# brain.net
KiCad netlist of a schematic drawn in EAGLE
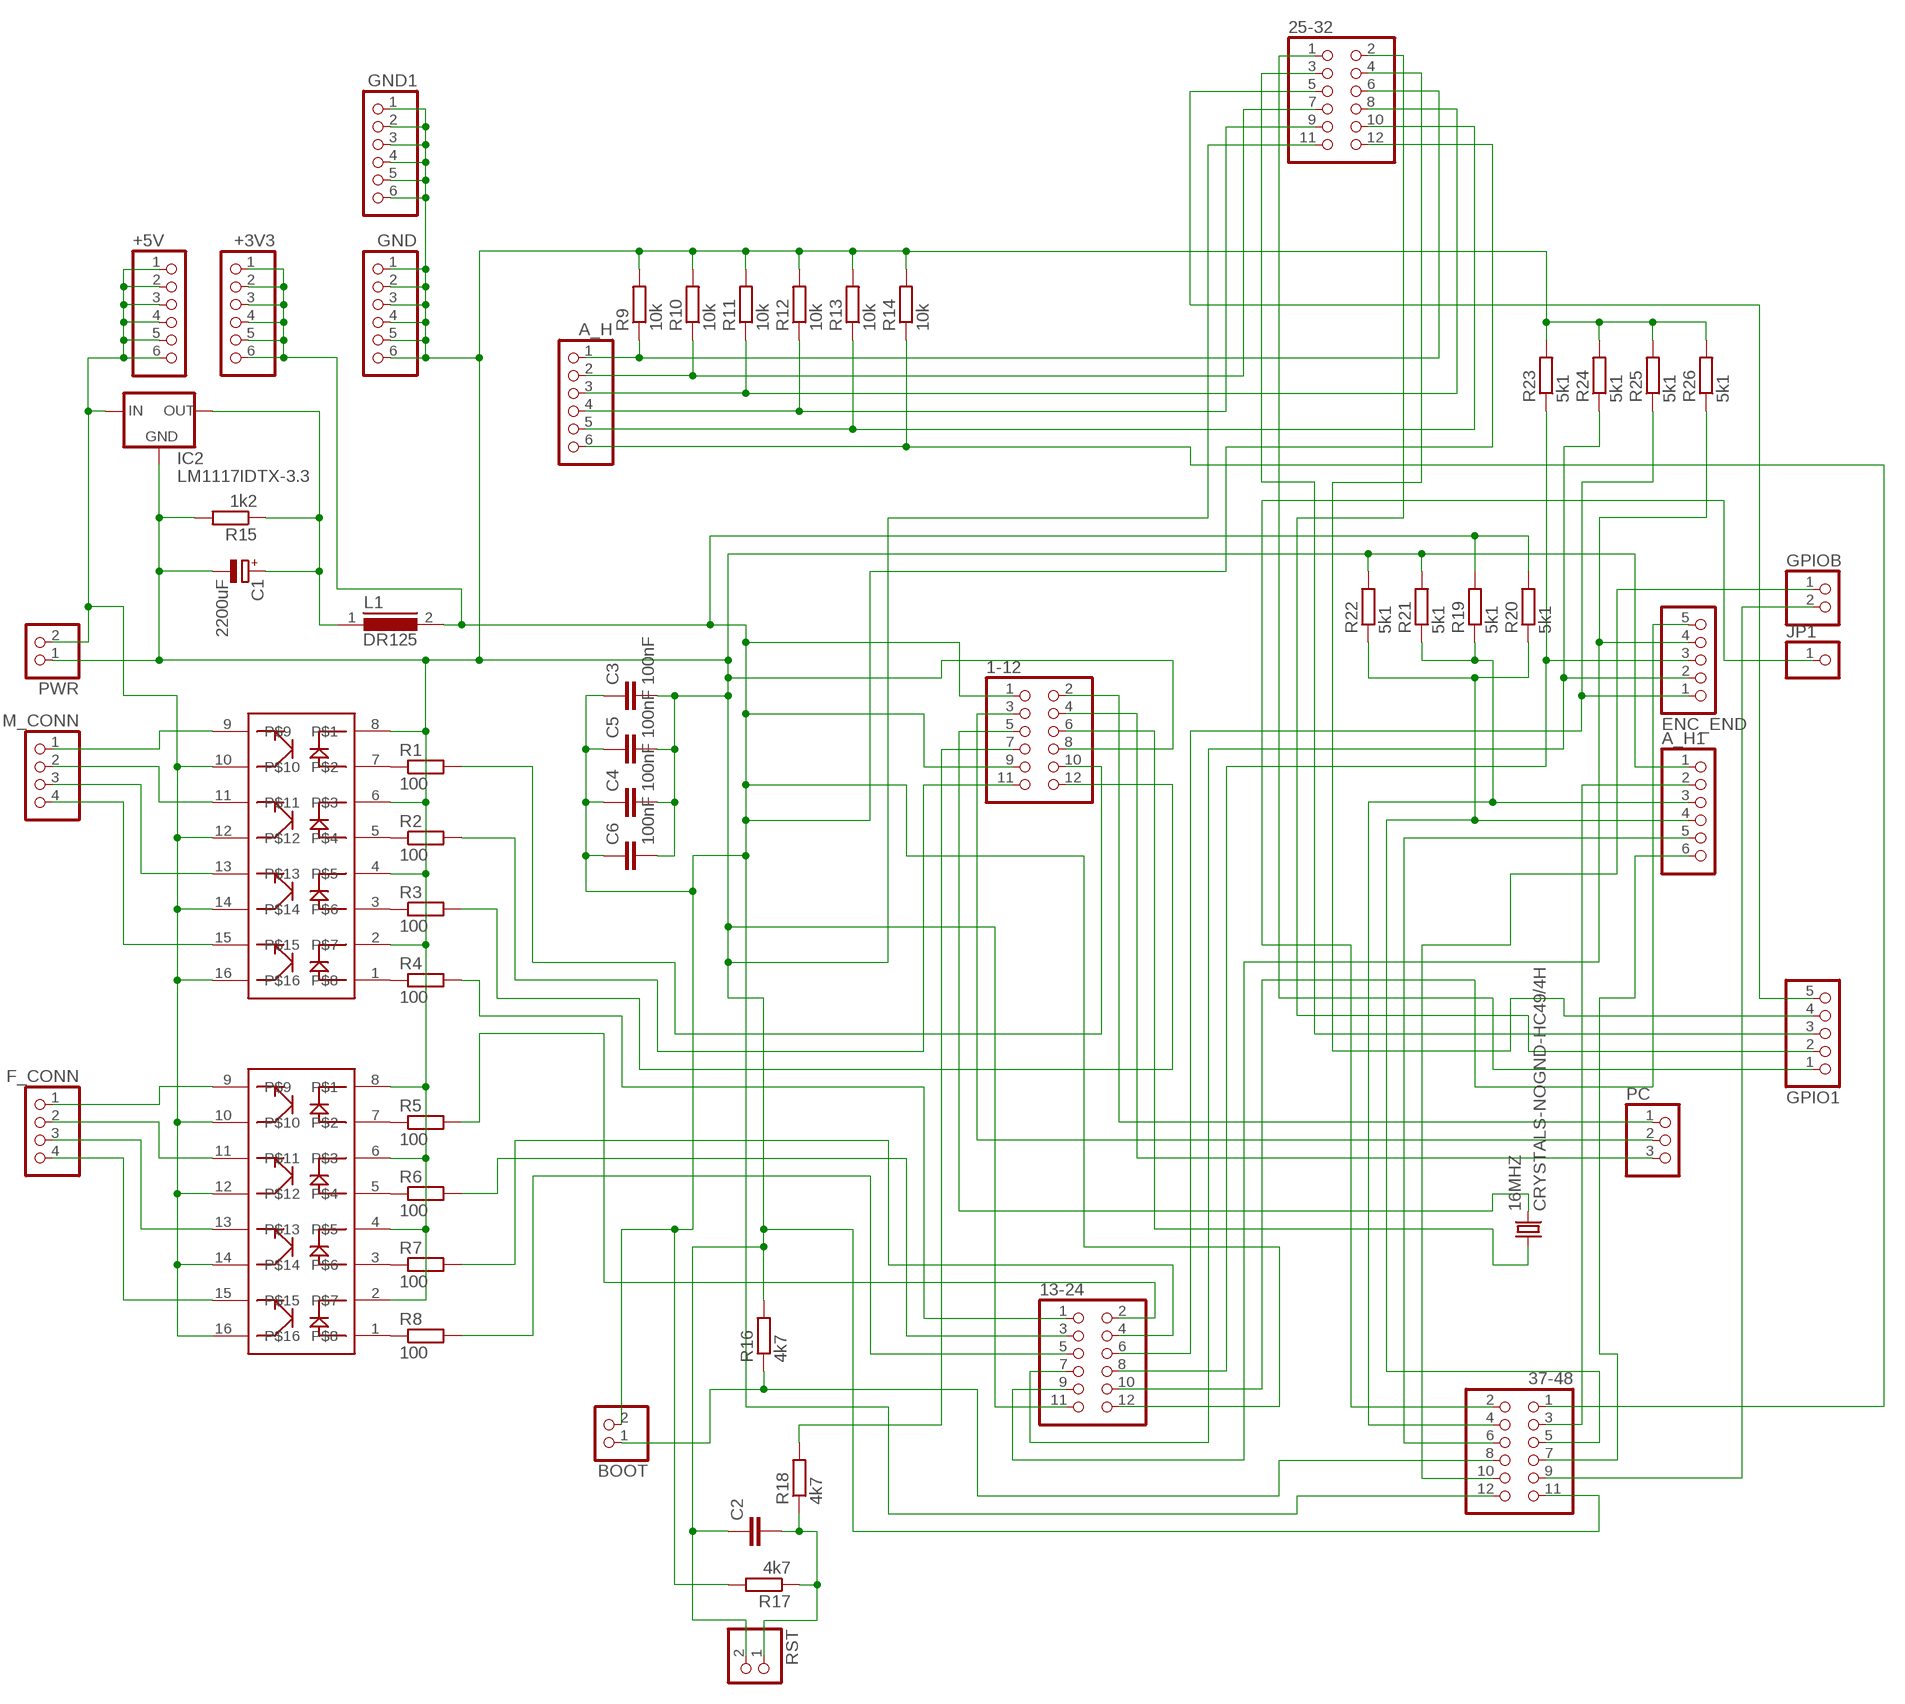
[diagram p0: schematic, sheet 1]

(export (version "E")
  (design (tool "Eeschema 10.0.6"))
  (components
    (comp (ref "+3V3")
      (value "PINHD-1X6")
      (footprint "eagle-import:1X06")
      (libsource (lib "eagle-import") (part "PINHD-1X6"))
    )
    (comp (ref "+5V")
      (value "PINHD-1X6")
      (footprint "eagle-import:1X06")
      (libsource (lib "eagle-import") (part "PINHD-1X6"))
    )
    (comp (ref "1-12")
      (value "PINHD-2X6")
      (footprint "eagle-import:2X06")
      (libsource (lib "eagle-import") (part "PINHD-2X6"))
    )
    (comp (ref "13-24")
      (value "PINHD-2X6")
      (footprint "eagle-import:2X06")
      (libsource (lib "eagle-import") (part "PINHD-2X6"))
    )
    (comp (ref "16MHZ")
      (value "CRYSTALS-NOGND-HC49/4H")
      (footprint "eagle-import:HC49")
      (libsource (lib "eagle-import") (part "CRYSTALS-NOGND-HC49/4H"))
    )
    (comp (ref "25-32")
      (value "PINHD-2X6")
      (footprint "eagle-import:2X06")
      (libsource (lib "eagle-import") (part "PINHD-2X6"))
    )
    (comp (ref "37-48")
      (value "PINHD-2X6")
      (footprint "eagle-import:2X06")
      (libsource (lib "eagle-import") (part "PINHD-2X6"))
    )
    (comp (ref "A_H")
      (value "PINHD-1X6")
      (footprint "eagle-import:1X06")
      (libsource (lib "eagle-import") (part "PINHD-1X6"))
    )
    (comp (ref "A_H1")
      (value "PINHD-1X6")
      (footprint "eagle-import:1X06")
      (libsource (lib "eagle-import") (part "PINHD-1X6"))
    )
    (comp (ref "BOOT")
      (value "PINHD-1X2")
      (footprint "eagle-import:1X02")
      (libsource (lib "eagle-import") (part "PINHD-1X2"))
    )
    (comp (ref "C1")
      (value "2200uF")
      (footprint "eagle-import:B45181D")
      (libsource (lib "eagle-import") (part "CPOL-EUB45181D"))
    )
    (comp (ref "C2")
      (value "C-EUC1206")
      (footprint "eagle-import:C1206")
      (libsource (lib "eagle-import") (part "C-EUC1206"))
    )
    (comp (ref "C3")
      (value "100nF")
      (footprint "eagle-import:C0805")
      (libsource (lib "eagle-import") (part "C-EUC0805"))
    )
    (comp (ref "C4")
      (value "100nF")
      (footprint "eagle-import:C0805")
      (libsource (lib "eagle-import") (part "C-EUC0805"))
    )
    (comp (ref "C5")
      (value "100nF")
      (footprint "eagle-import:C0805")
      (libsource (lib "eagle-import") (part "C-EUC0805"))
    )
    (comp (ref "C6")
      (value "100nF")
      (footprint "eagle-import:C0805")
      (libsource (lib "eagle-import") (part "C-EUC0805"))
    )
    (comp (ref "ENC_END")
      (value "PINHD-1X5")
      (footprint "eagle-import:1X05")
      (libsource (lib "eagle-import") (part "PINHD-1X5"))
    )
    (comp (ref "F_CONN")
      (value "PINHD-1X4")
      (footprint "eagle-import:1X04")
      (libsource (lib "eagle-import") (part "PINHD-1X4"))
    )
    (comp (ref "F_OPTO")
      (value "LTV847")
      (footprint "eagle-import:DIL16")
      (libsource (lib "eagle-import") (part "LTV847"))
    )
    (comp (ref "GND")
      (value "PINHD-1X6")
      (footprint "eagle-import:1X06")
      (libsource (lib "eagle-import") (part "PINHD-1X6"))
    )
    (comp (ref "GND1")
      (value "PINHD-1X6")
      (footprint "eagle-import:1X06")
      (libsource (lib "eagle-import") (part "PINHD-1X6"))
    )
    (comp (ref "GPIO1")
      (value "PINHD-1X5")
      (footprint "eagle-import:1X05")
      (libsource (lib "eagle-import") (part "PINHD-1X5"))
    )
    (comp (ref "GPIOB")
      (value "PINHD-1X2")
      (footprint "eagle-import:1X02")
      (libsource (lib "eagle-import") (part "PINHD-1X2"))
    )
    (comp (ref "IC2")
      (value "LM1117IDTX-3.3")
      (footprint "eagle-import:TO252")
      (libsource (lib "eagle-import") (part "LM1117IDTX-3.3"))
    )
    (comp (ref "JP1")
      (value "PINHD-1X1")
      (footprint "eagle-import:1X01")
      (libsource (lib "eagle-import") (part "PINHD-1X1"))
    )
    (comp (ref "L1")
      (value "DR125")
      (footprint "eagle-import:DR125")
      (libsource (lib "eagle-import") (part "DR125"))
    )
    (comp (ref "M_CONN")
      (value "PINHD-1X4")
      (footprint "eagle-import:1X04")
      (libsource (lib "eagle-import") (part "PINHD-1X4"))
    )
    (comp (ref "M_OPTO")
      (value "LTV847")
      (footprint "eagle-import:DIL16")
      (libsource (lib "eagle-import") (part "LTV847"))
    )
    (comp (ref "PC")
      (value "PINHD-1X3")
      (footprint "eagle-import:1X03")
      (libsource (lib "eagle-import") (part "PINHD-1X3"))
    )
    (comp (ref "PWR")
      (value "PINHD-1X2")
      (footprint "eagle-import:1X02")
      (libsource (lib "eagle-import") (part "PINHD-1X2"))
    )
    (comp (ref "R1")
      (value "100")
      (footprint "eagle-import:R1206")
      (libsource (lib "eagle-import") (part "R-EU_R1206"))
    )
    (comp (ref "R2")
      (value "100")
      (footprint "eagle-import:R1206")
      (libsource (lib "eagle-import") (part "R-EU_R1206"))
    )
    (comp (ref "R3")
      (value "100")
      (footprint "eagle-import:R1206")
      (libsource (lib "eagle-import") (part "R-EU_R1206"))
    )
    (comp (ref "R4")
      (value "100")
      (footprint "eagle-import:R1206")
      (libsource (lib "eagle-import") (part "R-EU_R1206"))
    )
    (comp (ref "R5")
      (value "100")
      (footprint "eagle-import:R1206")
      (libsource (lib "eagle-import") (part "R-EU_R1206"))
    )
    (comp (ref "R6")
      (value "100")
      (footprint "eagle-import:R1206")
      (libsource (lib "eagle-import") (part "R-EU_R1206"))
    )
    (comp (ref "R7")
      (value "100")
      (footprint "eagle-import:R1206")
      (libsource (lib "eagle-import") (part "R-EU_R1206"))
    )
    (comp (ref "R8")
      (value "100")
      (footprint "eagle-import:R1206")
      (libsource (lib "eagle-import") (part "R-EU_R1206"))
    )
    (comp (ref "R9")
      (value "10k")
      (footprint "eagle-import:R1206")
      (libsource (lib "eagle-import") (part "R-EU_R1206"))
    )
    (comp (ref "R10")
      (value "10k")
      (footprint "eagle-import:R1206")
      (libsource (lib "eagle-import") (part "R-EU_R1206"))
    )
    (comp (ref "R11")
      (value "10k")
      (footprint "eagle-import:R1206")
      (libsource (lib "eagle-import") (part "R-EU_R1206"))
    )
    (comp (ref "R12")
      (value "10k")
      (footprint "eagle-import:R1206")
      (libsource (lib "eagle-import") (part "R-EU_R1206"))
    )
    (comp (ref "R13")
      (value "10k")
      (footprint "eagle-import:R1206")
      (libsource (lib "eagle-import") (part "R-EU_R1206"))
    )
    (comp (ref "R14")
      (value "10k")
      (footprint "eagle-import:R1206")
      (libsource (lib "eagle-import") (part "R-EU_R1206"))
    )
    (comp (ref "R15")
      (value "1k2")
      (footprint "eagle-import:R1206")
      (libsource (lib "eagle-import") (part "R-EU_R1206"))
    )
    (comp (ref "R16")
      (value "4k7")
      (footprint "eagle-import:R1206")
      (libsource (lib "eagle-import") (part "R-EU_R1206"))
    )
    (comp (ref "R17")
      (value "4k7")
      (footprint "eagle-import:R1206")
      (libsource (lib "eagle-import") (part "R-EU_R1206"))
    )
    (comp (ref "R18")
      (value "4k7")
      (footprint "eagle-import:R1206")
      (libsource (lib "eagle-import") (part "R-EU_R1206"))
    )
    (comp (ref "R19")
      (value "5k1")
      (footprint "eagle-import:R1206")
      (libsource (lib "eagle-import") (part "R-EU_R1206"))
    )
    (comp (ref "R20")
      (value "5k1")
      (footprint "eagle-import:R1206")
      (libsource (lib "eagle-import") (part "R-EU_R1206"))
    )
    (comp (ref "R21")
      (value "5k1")
      (footprint "eagle-import:R1206")
      (libsource (lib "eagle-import") (part "R-EU_R1206"))
    )
    (comp (ref "R22")
      (value "5k1")
      (footprint "eagle-import:R1206")
      (libsource (lib "eagle-import") (part "R-EU_R1206"))
    )
    (comp (ref "R23")
      (value "5k1")
      (footprint "eagle-import:R1206")
      (libsource (lib "eagle-import") (part "R-EU_R1206"))
    )
    (comp (ref "R24")
      (value "5k1")
      (footprint "eagle-import:R1206")
      (libsource (lib "eagle-import") (part "R-EU_R1206"))
    )
    (comp (ref "R25")
      (value "5k1")
      (footprint "eagle-import:R1206")
      (libsource (lib "eagle-import") (part "R-EU_R1206"))
    )
    (comp (ref "R26")
      (value "5k1")
      (footprint "eagle-import:R1206")
      (libsource (lib "eagle-import") (part "R-EU_R1206"))
    )
    (comp (ref "RST")
      (value "PINHD-1X2")
      (footprint "eagle-import:1X02")
      (libsource (lib "eagle-import") (part "PINHD-1X2"))
    )
  )
  (nets
    (net (code "1") (name "Net-(+3V3-Pad1)") (class "Default")
      (node (ref "+3V3") (pin "1") (pinfunction "1_1") (pintype "passive"))
      (node (ref "+3V3") (pin "2") (pinfunction "2_2") (pintype "passive"))
      (node (ref "+3V3") (pin "3") (pinfunction "3_3") (pintype "passive"))
      (node (ref "+3V3") (pin "4") (pinfunction "4_4") (pintype "passive"))
      (node (ref "+3V3") (pin "5") (pinfunction "5_5") (pintype "passive"))
      (node (ref "+3V3") (pin "6") (pinfunction "6_6") (pintype "passive"))
      (node (ref "1-12") (pin "1") (pinfunction "1_1") (pintype "passive"))
      (node (ref "1-12") (pin "9") (pinfunction "9_9") (pintype "passive"))
      (node (ref "13-24") (pin "12") (pinfunction "12_12") (pintype "passive"))
      (node (ref "25-32") (pin "12") (pinfunction "12_12") (pintype "passive"))
      (node (ref "37-48") (pin "12") (pinfunction "12_12") (pintype "passive"))
      (node (ref "BOOT") (pin "2") (pinfunction "2_2") (pintype "passive"))
      (node (ref "C3") (pin "1") (pinfunction "1_1") (pintype "passive"))
      (node (ref "C4") (pin "1") (pinfunction "1_1") (pintype "passive"))
      (node (ref "C5") (pin "1") (pinfunction "1_1") (pintype "passive"))
      (node (ref "C6") (pin "1") (pinfunction "1_1") (pintype "passive"))
      (node (ref "L1") (pin "2") (pinfunction "2_2") (pintype "passive"))
      (node (ref "R17") (pin "2") (pinfunction "2_2") (pintype "passive"))
      (node (ref "R19") (pin "2") (pinfunction "2_2") (pintype "passive"))
      (node (ref "R20") (pin "2") (pinfunction "2_2") (pintype "passive"))
    )
    (net (code "2") (name "Net-(1-12-Pad2)") (class "Default")
      (node (ref "1-12") (pin "2") (pinfunction "2_2") (pintype "passive"))
      (node (ref "PC") (pin "1") (pinfunction "1_1") (pintype "passive"))
    )
    (net (code "3") (name "Net-(1-12-Pad3)") (class "Default")
      (node (ref "1-12") (pin "3") (pinfunction "3_3") (pintype "passive"))
      (node (ref "PC") (pin "2") (pinfunction "2_2") (pintype "passive"))
    )
    (net (code "4") (name "Net-(1-12-Pad4)") (class "Default")
      (node (ref "1-12") (pin "4") (pinfunction "4_4") (pintype "passive"))
      (node (ref "PC") (pin "3") (pinfunction "3_3") (pintype "passive"))
    )
    (net (code "5") (name "Net-(1-12-Pad5)") (class "Default")
      (node (ref "1-12") (pin "5") (pinfunction "5_5") (pintype "passive"))
      (node (ref "16MHZ") (pin "2") (pinfunction "2_2") (pintype "passive"))
    )
    (net (code "6") (name "Net-(1-12-Pad6)") (class "Default")
      (node (ref "1-12") (pin "6") (pinfunction "6_6") (pintype "passive"))
      (node (ref "16MHZ") (pin "1") (pinfunction "1_1") (pintype "passive"))
    )
    (net (code "7") (name "Net-(1-12-Pad7)") (class "Default")
      (node (ref "1-12") (pin "7") (pinfunction "7_7") (pintype "passive"))
      (node (ref "R18") (pin "2") (pinfunction "2_2") (pintype "passive"))
    )
    (net (code "8") (name "Net-(1-12-Pad10)") (class "Default")
      (node (ref "1-12") (pin "10") (pinfunction "10_10") (pintype "passive"))
      (node (ref "R1") (pin "2") (pinfunction "2_2") (pintype "passive"))
    )
    (net (code "9") (name "Net-(1-12-Pad11)") (class "Default")
      (node (ref "1-12") (pin "11") (pinfunction "11_11") (pintype "passive"))
      (node (ref "R2") (pin "2") (pinfunction "2_2") (pintype "passive"))
    )
    (net (code "10") (name "Net-(1-12-Pad12)") (class "Default")
      (node (ref "1-12") (pin "12") (pinfunction "12_12") (pintype "passive"))
      (node (ref "R3") (pin "2") (pinfunction "2_2") (pintype "passive"))
    )
    (net (code "11") (name "Net-(13-24-Pad1)") (class "Default")
      (node (ref "13-24") (pin "1") (pinfunction "1_1") (pintype "passive"))
      (node (ref "R4") (pin "2") (pinfunction "2_2") (pintype "passive"))
    )
    (net (code "12") (name "Net-(13-24-Pad2)") (class "Default")
      (node (ref "13-24") (pin "2") (pinfunction "2_2") (pintype "passive"))
      (node (ref "R5") (pin "2") (pinfunction "2_2") (pintype "passive"))
    )
    (net (code "13") (name "Net-(13-24-Pad3)") (class "Default")
      (node (ref "13-24") (pin "3") (pinfunction "3_3") (pintype "passive"))
      (node (ref "R6") (pin "2") (pinfunction "2_2") (pintype "passive"))
    )
    (net (code "14") (name "Net-(13-24-Pad4)") (class "Default")
      (node (ref "13-24") (pin "4") (pinfunction "4_4") (pintype "passive"))
      (node (ref "R7") (pin "2") (pinfunction "2_2") (pintype "passive"))
    )
    (net (code "15") (name "Net-(13-24-Pad5)") (class "Default")
      (node (ref "13-24") (pin "5") (pinfunction "5_5") (pintype "passive"))
      (node (ref "R8") (pin "2") (pinfunction "2_2") (pintype "passive"))
    )
    (net (code "16") (name "Net-(13-24-Pad6)") (class "Default")
      (node (ref "13-24") (pin "6") (pinfunction "6_6") (pintype "passive"))
      (node (ref "ENC_END") (pin "1") (pinfunction "1_1") (pintype "passive"))
      (node (ref "R25") (pin "1") (pinfunction "1_1") (pintype "passive"))
    )
    (net (code "17") (name "Net-(13-24-Pad7)") (class "Default")
      (node (ref "13-24") (pin "7") (pinfunction "7_7") (pintype "passive"))
      (node (ref "ENC_END") (pin "2") (pinfunction "2_2") (pintype "passive"))
      (node (ref "R24") (pin "1") (pinfunction "1_1") (pintype "passive"))
    )
    (net (code "18") (name "Net-(13-24-Pad8)") (class "Default")
      (node (ref "13-24") (pin "8") (pinfunction "8_8") (pintype "passive"))
      (node (ref "ENC_END") (pin "3") (pinfunction "3_3") (pintype "passive"))
      (node (ref "R23") (pin "1") (pinfunction "1_1") (pintype "passive"))
    )
    (net (code "19") (name "Net-(13-24-Pad9)") (class "Default")
      (node (ref "13-24") (pin "9") (pinfunction "9_9") (pintype "passive"))
      (node (ref "ENC_END") (pin "4") (pinfunction "4_4") (pintype "passive"))
      (node (ref "R26") (pin "1") (pinfunction "1_1") (pintype "passive"))
    )
    (net (code "20") (name "Net-(13-24-Pad10)") (class "Default")
      (node (ref "13-24") (pin "10") (pinfunction "10_10") (pintype "passive"))
      (node (ref "ENC_END") (pin "5") (pinfunction "5_5") (pintype "passive"))
    )
    (net (code "21") (name "Net-(25-32-Pad1)") (class "Default")
      (node (ref "25-32") (pin "1") (pinfunction "1_1") (pintype "passive"))
      (node (ref "GPIO1") (pin "1") (pinfunction "1_1") (pintype "passive"))
    )
    (net (code "22") (name "Net-(25-32-Pad2)") (class "Default")
      (node (ref "25-32") (pin "2") (pinfunction "2_2") (pintype "passive"))
      (node (ref "GPIO1") (pin "2") (pinfunction "2_2") (pintype "passive"))
    )
    (net (code "23") (name "Net-(25-32-Pad3)") (class "Default")
      (node (ref "25-32") (pin "3") (pinfunction "3_3") (pintype "passive"))
      (node (ref "GPIO1") (pin "3") (pinfunction "3_3") (pintype "passive"))
    )
    (net (code "24") (name "Net-(25-32-Pad4)") (class "Default")
      (node (ref "25-32") (pin "4") (pinfunction "4_4") (pintype "passive"))
      (node (ref "GPIO1") (pin "4") (pinfunction "4_4") (pintype "passive"))
    )
    (net (code "25") (name "Net-(25-32-Pad5)") (class "Default")
      (node (ref "25-32") (pin "5") (pinfunction "5_5") (pintype "passive"))
      (node (ref "GPIO1") (pin "5") (pinfunction "5_5") (pintype "passive"))
    )
    (net (code "26") (name "Net-(25-32-Pad6)") (class "Default")
      (node (ref "25-32") (pin "6") (pinfunction "6_6") (pintype "passive"))
      (node (ref "A_H") (pin "1") (pinfunction "1_1") (pintype "passive"))
      (node (ref "R9") (pin "1") (pinfunction "1_1") (pintype "passive"))
    )
    (net (code "27") (name "Net-(25-32-Pad7)") (class "Default")
      (node (ref "25-32") (pin "7") (pinfunction "7_7") (pintype "passive"))
      (node (ref "A_H") (pin "2") (pinfunction "2_2") (pintype "passive"))
      (node (ref "R10") (pin "1") (pinfunction "1_1") (pintype "passive"))
    )
    (net (code "28") (name "Net-(25-32-Pad8)") (class "Default")
      (node (ref "25-32") (pin "8") (pinfunction "8_8") (pintype "passive"))
      (node (ref "A_H") (pin "3") (pinfunction "3_3") (pintype "passive"))
      (node (ref "R11") (pin "1") (pinfunction "1_1") (pintype "passive"))
    )
    (net (code "29") (name "Net-(25-32-Pad9)") (class "Default")
      (node (ref "25-32") (pin "9") (pinfunction "9_9") (pintype "passive"))
      (node (ref "A_H") (pin "4") (pinfunction "4_4") (pintype "passive"))
      (node (ref "R12") (pin "1") (pinfunction "1_1") (pintype "passive"))
    )
    (net (code "30") (name "Net-(25-32-Pad10)") (class "Default")
      (node (ref "25-32") (pin "10") (pinfunction "10_10") (pintype "passive"))
      (node (ref "A_H") (pin "5") (pinfunction "5_5") (pintype "passive"))
      (node (ref "R13") (pin "1") (pinfunction "1_1") (pintype "passive"))
    )
    (net (code "31") (name "Net-(37-48-Pad1)") (class "Default")
      (node (ref "37-48") (pin "1") (pinfunction "1_1") (pintype "passive"))
      (node (ref "A_H") (pin "6") (pinfunction "6_6") (pintype "passive"))
      (node (ref "R14") (pin "1") (pinfunction "1_1") (pintype "passive"))
    )
    (net (code "32") (name "Net-(37-48-Pad2)") (class "Default")
      (node (ref "37-48") (pin "2") (pinfunction "2_2") (pintype "passive"))
      (node (ref "JP1") (pin "1") (pinfunction "1_1") (pintype "passive"))
    )
    (net (code "33") (name "Net-(37-48-Pad3)") (class "Default")
      (node (ref "37-48") (pin "3") (pinfunction "3_3") (pintype "passive"))
      (node (ref "A_H1") (pin "2") (pinfunction "2_2") (pintype "passive"))
    )
    (net (code "34") (name "Net-(37-48-Pad4)") (class "Default")
      (node (ref "37-48") (pin "4") (pinfunction "4_4") (pintype "passive"))
      (node (ref "A_H1") (pin "3") (pinfunction "3_3") (pintype "passive"))
      (node (ref "R19") (pin "1") (pinfunction "1_1") (pintype "passive"))
      (node (ref "R21") (pin "1") (pinfunction "1_1") (pintype "passive"))
    )
    (net (code "35") (name "Net-(37-48-Pad5)") (class "Default")
      (node (ref "37-48") (pin "5") (pinfunction "5_5") (pintype "passive"))
      (node (ref "A_H1") (pin "4") (pinfunction "4_4") (pintype "passive"))
      (node (ref "R20") (pin "1") (pinfunction "1_1") (pintype "passive"))
      (node (ref "R22") (pin "1") (pinfunction "1_1") (pintype "passive"))
    )
    (net (code "36") (name "Net-(37-48-Pad6)") (class "Default")
      (node (ref "37-48") (pin "6") (pinfunction "6_6") (pintype "passive"))
      (node (ref "A_H1") (pin "5") (pinfunction "5_5") (pintype "passive"))
    )
    (net (code "37") (name "Net-(37-48-Pad7)") (class "Default")
      (node (ref "37-48") (pin "7") (pinfunction "7_7") (pintype "passive"))
      (node (ref "A_H1") (pin "6") (pinfunction "6_6") (pintype "passive"))
    )
    (net (code "38") (name "Net-(37-48-Pad8)") (class "Default")
      (node (ref "37-48") (pin "8") (pinfunction "8_8") (pintype "passive"))
      (node (ref "BOOT") (pin "1") (pinfunction "1_1") (pintype "passive"))
      (node (ref "R16") (pin "1") (pinfunction "1_1") (pintype "passive"))
    )
    (net (code "39") (name "Net-(37-48-Pad9)") (class "Default")
      (node (ref "37-48") (pin "9") (pinfunction "9_9") (pintype "passive"))
      (node (ref "GPIOB") (pin "2") (pinfunction "2_2") (pintype "passive"))
    )
    (net (code "40") (name "Net-(37-48-Pad10)") (class "Default")
      (node (ref "37-48") (pin "10") (pinfunction "10_10") (pintype "passive"))
      (node (ref "GPIOB") (pin "1") (pinfunction "1_1") (pintype "passive"))
    )
    (net (code "41") (name "Net-(C2-Pad2)") (class "Default")
      (node (ref "C2") (pin "2") (pinfunction "2_2") (pintype "passive"))
      (node (ref "R17") (pin "1") (pinfunction "1_1") (pintype "passive"))
      (node (ref "R18") (pin "1") (pinfunction "1_1") (pintype "passive"))
      (node (ref "RST") (pin "1") (pinfunction "1_1") (pintype "passive"))
    )
    (net (code "42") (name "Net-(F_OPTO-P$1)") (class "Default")
      (node (ref "1-12") (pin "8") (pinfunction "8_8") (pintype "passive"))
      (node (ref "13-24") (pin "11") (pinfunction "11_11") (pintype "passive"))
      (node (ref "25-32") (pin "11") (pinfunction "11_11") (pintype "passive"))
      (node (ref "37-48") (pin "11") (pinfunction "11_11") (pintype "passive"))
      (node (ref "A_H1") (pin "1") (pinfunction "1_1") (pintype "passive"))
      (node (ref "C1") (pin "-") (pinfunction "-_-") (pintype "passive"))
      (node (ref "C2") (pin "1") (pinfunction "1_1") (pintype "passive"))
      (node (ref "C3") (pin "2") (pinfunction "2_2") (pintype "passive"))
      (node (ref "C4") (pin "2") (pinfunction "2_2") (pintype "passive"))
      (node (ref "C5") (pin "2") (pinfunction "2_2") (pintype "passive"))
      (node (ref "C6") (pin "2") (pinfunction "2_2") (pintype "passive"))
      (node (ref "F_OPTO") (pin "2") (pinfunction "P$7_2") (pintype "passive"))
      (node (ref "F_OPTO") (pin "4") (pinfunction "P$5_4") (pintype "passive"))
      (node (ref "F_OPTO") (pin "6") (pinfunction "P$3_6") (pintype "passive"))
      (node (ref "F_OPTO") (pin "8") (pinfunction "P$1_8") (pintype "passive"))
      (node (ref "GND") (pin "1") (pinfunction "1_1") (pintype "passive"))
      (node (ref "GND") (pin "2") (pinfunction "2_2") (pintype "passive"))
      (node (ref "GND") (pin "3") (pinfunction "3_3") (pintype "passive"))
      (node (ref "GND") (pin "4") (pinfunction "4_4") (pintype "passive"))
      (node (ref "GND") (pin "5") (pinfunction "5_5") (pintype "passive"))
      (node (ref "GND") (pin "6") (pinfunction "6_6") (pintype "passive"))
      (node (ref "GND1") (pin "1") (pinfunction "1_1") (pintype "passive"))
      (node (ref "GND1") (pin "2") (pinfunction "2_2") (pintype "passive"))
      (node (ref "GND1") (pin "3") (pinfunction "3_3") (pintype "passive"))
      (node (ref "GND1") (pin "4") (pinfunction "4_4") (pintype "passive"))
      (node (ref "GND1") (pin "5") (pinfunction "5_5") (pintype "passive"))
      (node (ref "GND1") (pin "6") (pinfunction "6_6") (pintype "passive"))
      (node (ref "IC2") (pin "1") (pinfunction "GND_1") (pintype "input"))
      (node (ref "M_OPTO") (pin "2") (pinfunction "P$7_2") (pintype "passive"))
      (node (ref "M_OPTO") (pin "4") (pinfunction "P$5_4") (pintype "passive"))
      (node (ref "M_OPTO") (pin "6") (pinfunction "P$3_6") (pintype "passive"))
      (node (ref "M_OPTO") (pin "8") (pinfunction "P$1_8") (pintype "passive"))
      (node (ref "PWR") (pin "1") (pinfunction "1_1") (pintype "passive"))
      (node (ref "R10") (pin "2") (pinfunction "2_2") (pintype "passive"))
      (node (ref "R11") (pin "2") (pinfunction "2_2") (pintype "passive"))
      (node (ref "R12") (pin "2") (pinfunction "2_2") (pintype "passive"))
      (node (ref "R13") (pin "2") (pinfunction "2_2") (pintype "passive"))
      (node (ref "R14") (pin "2") (pinfunction "2_2") (pintype "passive"))
      (node (ref "R15") (pin "2") (pinfunction "2_2") (pintype "passive"))
      (node (ref "R16") (pin "2") (pinfunction "2_2") (pintype "passive"))
      (node (ref "R21") (pin "2") (pinfunction "2_2") (pintype "passive"))
      (node (ref "R22") (pin "2") (pinfunction "2_2") (pintype "passive"))
      (node (ref "R23") (pin "2") (pinfunction "2_2") (pintype "passive"))
      (node (ref "R24") (pin "2") (pinfunction "2_2") (pintype "passive"))
      (node (ref "R25") (pin "2") (pinfunction "2_2") (pintype "passive"))
      (node (ref "R26") (pin "2") (pinfunction "2_2") (pintype "passive"))
      (node (ref "R9") (pin "2") (pinfunction "2_2") (pintype "passive"))
      (node (ref "RST") (pin "2") (pinfunction "2_2") (pintype "passive"))
    )
    (net (code "43") (name "Net-(F_OPTO-P$2)") (class "Default")
      (node (ref "F_OPTO") (pin "7") (pinfunction "P$2_7") (pintype "passive"))
      (node (ref "R5") (pin "1") (pinfunction "1_1") (pintype "passive"))
    )
    (net (code "44") (name "Net-(F_OPTO-P$4)") (class "Default")
      (node (ref "F_OPTO") (pin "5") (pinfunction "P$4_5") (pintype "passive"))
      (node (ref "R6") (pin "1") (pinfunction "1_1") (pintype "passive"))
    )
    (net (code "45") (name "Net-(F_OPTO-P$6)") (class "Default")
      (node (ref "F_OPTO") (pin "3") (pinfunction "P$6_3") (pintype "passive"))
      (node (ref "R7") (pin "1") (pinfunction "1_1") (pintype "passive"))
    )
    (net (code "46") (name "Net-(F_OPTO-P$8)") (class "Default")
      (node (ref "F_OPTO") (pin "1") (pinfunction "P$8_1") (pintype "passive"))
      (node (ref "R8") (pin "1") (pinfunction "1_1") (pintype "passive"))
    )
    (net (code "47") (name "Net-(F_OPTO-P$9)") (class "Default")
      (node (ref "F_CONN") (pin "1") (pinfunction "1_1") (pintype "passive"))
      (node (ref "F_OPTO") (pin "9") (pinfunction "P$9_9") (pintype "passive"))
    )
    (net (code "48") (name "Net-(F_OPTO-P$10)") (class "Default")
      (node (ref "+5V") (pin "1") (pinfunction "1_1") (pintype "passive"))
      (node (ref "+5V") (pin "2") (pinfunction "2_2") (pintype "passive"))
      (node (ref "+5V") (pin "3") (pinfunction "3_3") (pintype "passive"))
      (node (ref "+5V") (pin "4") (pinfunction "4_4") (pintype "passive"))
      (node (ref "+5V") (pin "5") (pinfunction "5_5") (pintype "passive"))
      (node (ref "+5V") (pin "6") (pinfunction "6_6") (pintype "passive"))
      (node (ref "F_OPTO") (pin "10") (pinfunction "P$10_10") (pintype "passive"))
      (node (ref "F_OPTO") (pin "12") (pinfunction "P$12_12") (pintype "passive"))
      (node (ref "F_OPTO") (pin "14") (pinfunction "P$14_14") (pintype "passive"))
      (node (ref "F_OPTO") (pin "16") (pinfunction "P$16_16") (pintype "passive"))
      (node (ref "IC2") (pin "2") (pinfunction "IN_2") (pintype "input"))
      (node (ref "M_OPTO") (pin "10") (pinfunction "P$10_10") (pintype "passive"))
      (node (ref "M_OPTO") (pin "12") (pinfunction "P$12_12") (pintype "passive"))
      (node (ref "M_OPTO") (pin "14") (pinfunction "P$14_14") (pintype "passive"))
      (node (ref "M_OPTO") (pin "16") (pinfunction "P$16_16") (pintype "passive"))
      (node (ref "PWR") (pin "2") (pinfunction "2_2") (pintype "passive"))
    )
    (net (code "49") (name "Net-(F_OPTO-P$11)") (class "Default")
      (node (ref "F_CONN") (pin "2") (pinfunction "2_2") (pintype "passive"))
      (node (ref "F_OPTO") (pin "11") (pinfunction "P$11_11") (pintype "passive"))
    )
    (net (code "50") (name "Net-(F_OPTO-P$13)") (class "Default")
      (node (ref "F_CONN") (pin "3") (pinfunction "3_3") (pintype "passive"))
      (node (ref "F_OPTO") (pin "13") (pinfunction "P$13_13") (pintype "passive"))
    )
    (net (code "51") (name "Net-(F_OPTO-P$15)") (class "Default")
      (node (ref "F_CONN") (pin "4") (pinfunction "4_4") (pintype "passive"))
      (node (ref "F_OPTO") (pin "15") (pinfunction "P$15_15") (pintype "passive"))
    )
    (net (code "52") (name "Net-(IC2-OUT)") (class "Default")
      (node (ref "C1") (pin "+") (pinfunction "+_+") (pintype "passive"))
      (node (ref "IC2") (pin "TAB") (pinfunction "OUT_TAB") (pintype "passive"))
      (node (ref "L1") (pin "1") (pinfunction "1_1") (pintype "passive"))
      (node (ref "R15") (pin "1") (pinfunction "1_1") (pintype "passive"))
    )
    (net (code "53") (name "Net-(M_OPTO-P$2)") (class "Default")
      (node (ref "M_OPTO") (pin "7") (pinfunction "P$2_7") (pintype "passive"))
      (node (ref "R1") (pin "1") (pinfunction "1_1") (pintype "passive"))
    )
    (net (code "54") (name "Net-(M_OPTO-P$4)") (class "Default")
      (node (ref "M_OPTO") (pin "5") (pinfunction "P$4_5") (pintype "passive"))
      (node (ref "R2") (pin "1") (pinfunction "1_1") (pintype "passive"))
    )
    (net (code "55") (name "Net-(M_OPTO-P$6)") (class "Default")
      (node (ref "M_OPTO") (pin "3") (pinfunction "P$6_3") (pintype "passive"))
      (node (ref "R3") (pin "1") (pinfunction "1_1") (pintype "passive"))
    )
    (net (code "56") (name "Net-(M_OPTO-P$8)") (class "Default")
      (node (ref "M_OPTO") (pin "1") (pinfunction "P$8_1") (pintype "passive"))
      (node (ref "R4") (pin "1") (pinfunction "1_1") (pintype "passive"))
    )
    (net (code "57") (name "Net-(M_OPTO-P$9)") (class "Default")
      (node (ref "M_CONN") (pin "1") (pinfunction "1_1") (pintype "passive"))
      (node (ref "M_OPTO") (pin "9") (pinfunction "P$9_9") (pintype "passive"))
    )
    (net (code "58") (name "Net-(M_OPTO-P$11)") (class "Default")
      (node (ref "M_CONN") (pin "2") (pinfunction "2_2") (pintype "passive"))
      (node (ref "M_OPTO") (pin "11") (pinfunction "P$11_11") (pintype "passive"))
    )
    (net (code "59") (name "Net-(M_OPTO-P$13)") (class "Default")
      (node (ref "M_CONN") (pin "3") (pinfunction "3_3") (pintype "passive"))
      (node (ref "M_OPTO") (pin "13") (pinfunction "P$13_13") (pintype "passive"))
    )
    (net (code "60") (name "Net-(M_OPTO-P$15)") (class "Default")
      (node (ref "M_CONN") (pin "4") (pinfunction "4_4") (pintype "passive"))
      (node (ref "M_OPTO") (pin "15") (pinfunction "P$15_15") (pintype "passive"))
    )
  )
)
